# RF-Gen_Controller.net
KiCad netlist of a schematic drawn in EAGLE
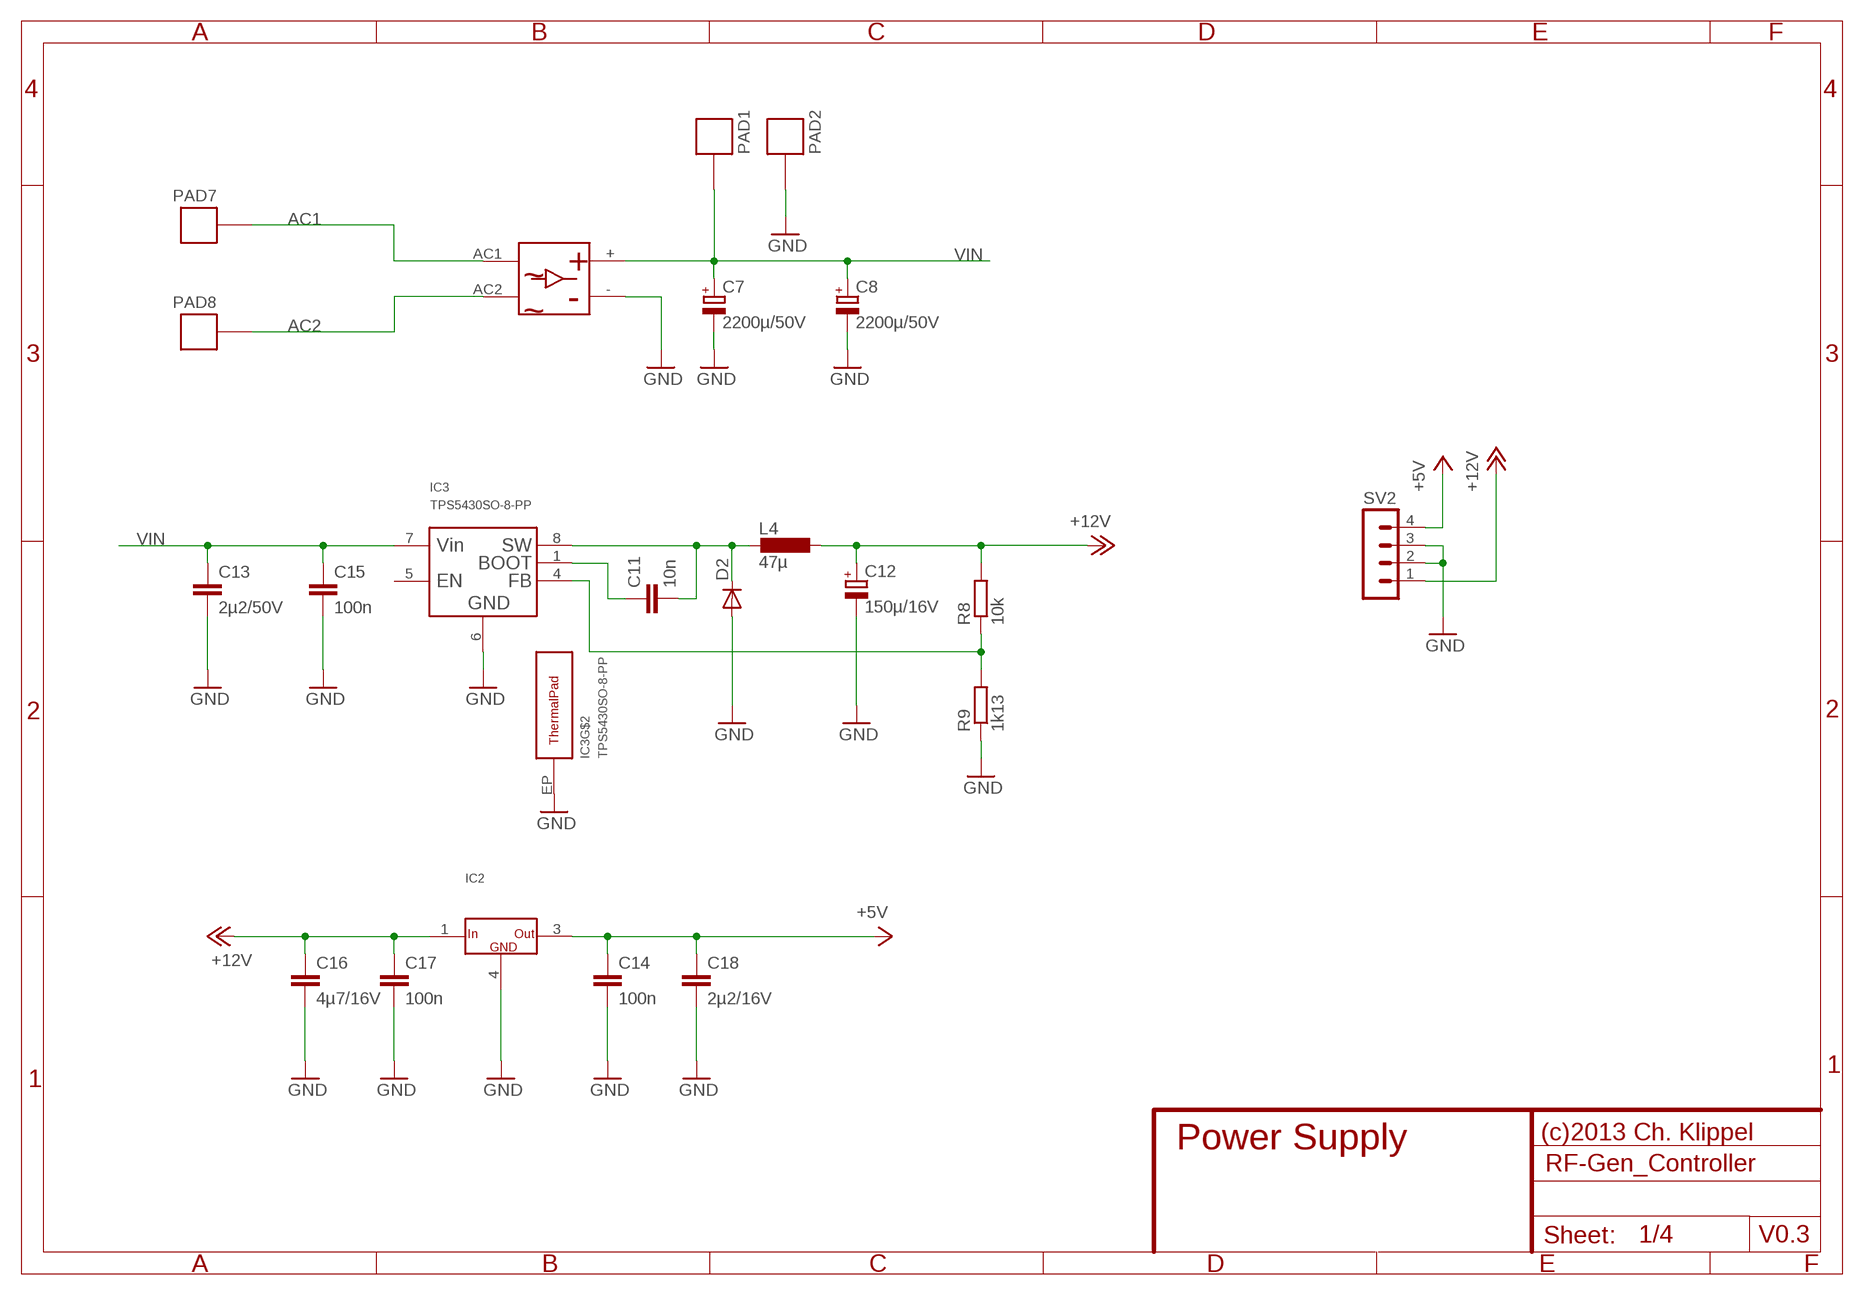
[diagram p0: schematic, sheet 1]
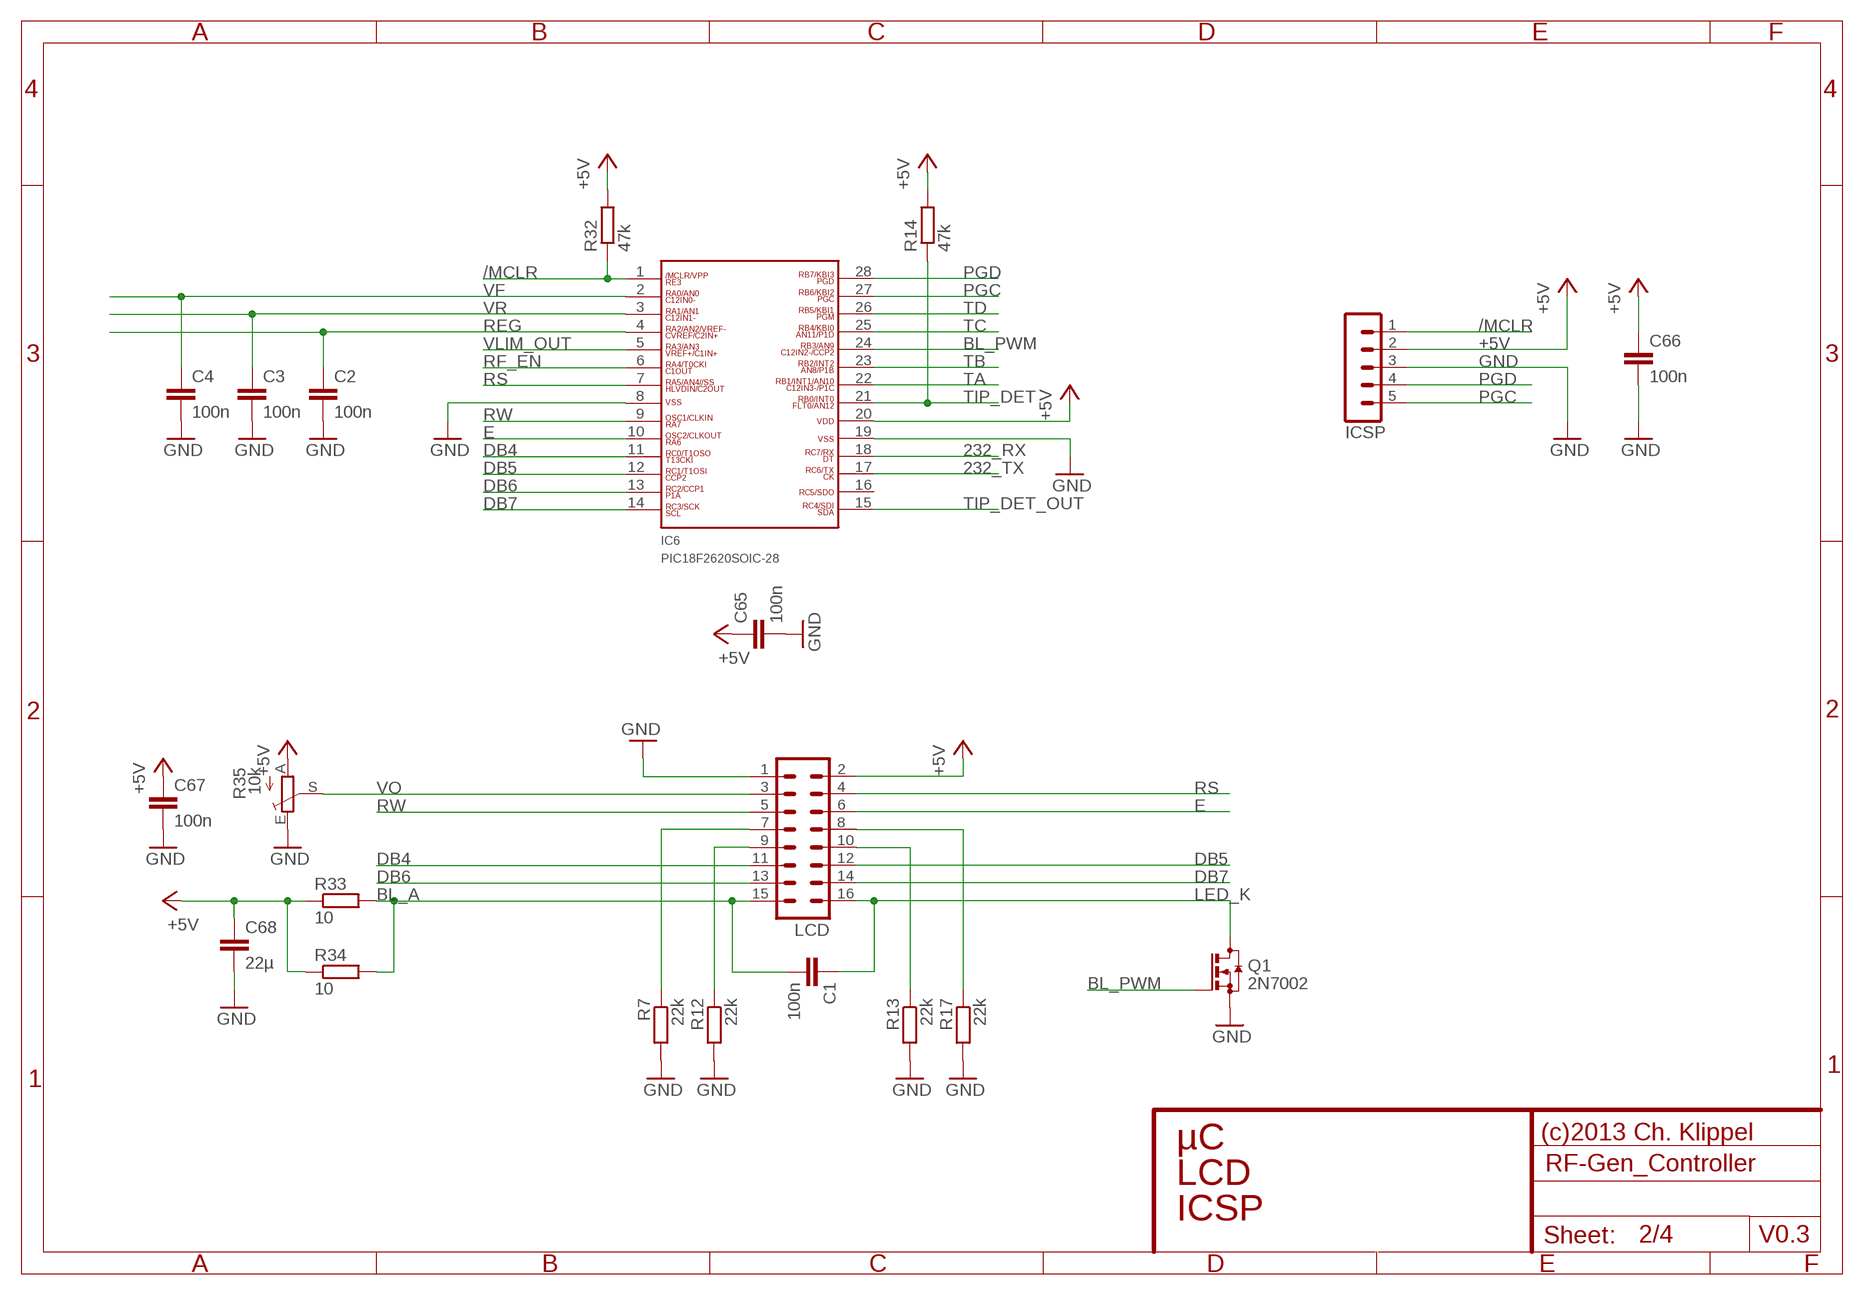
[diagram p1: schematic, sheet 2]
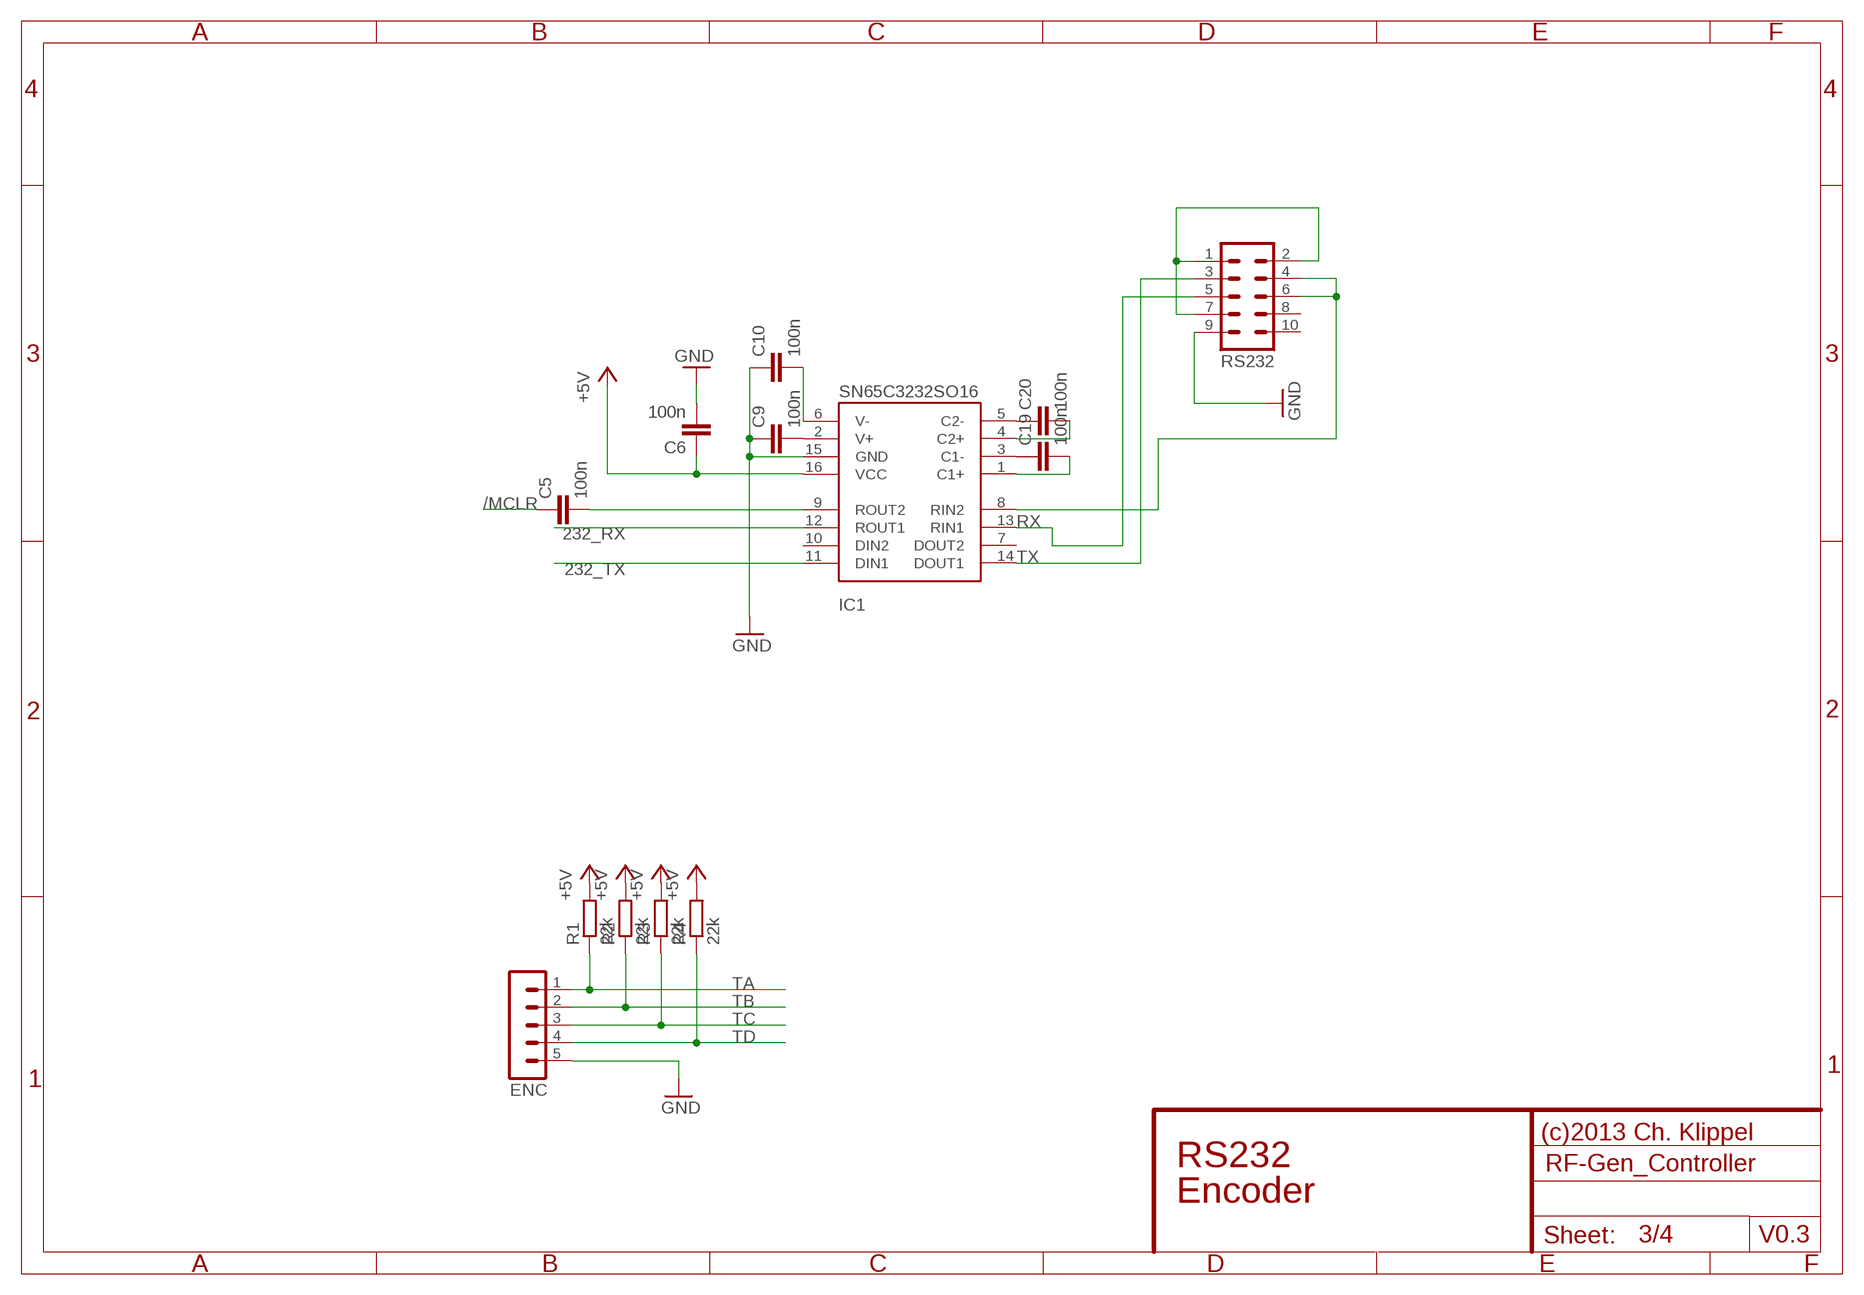
[diagram p2: schematic, sheet 3]
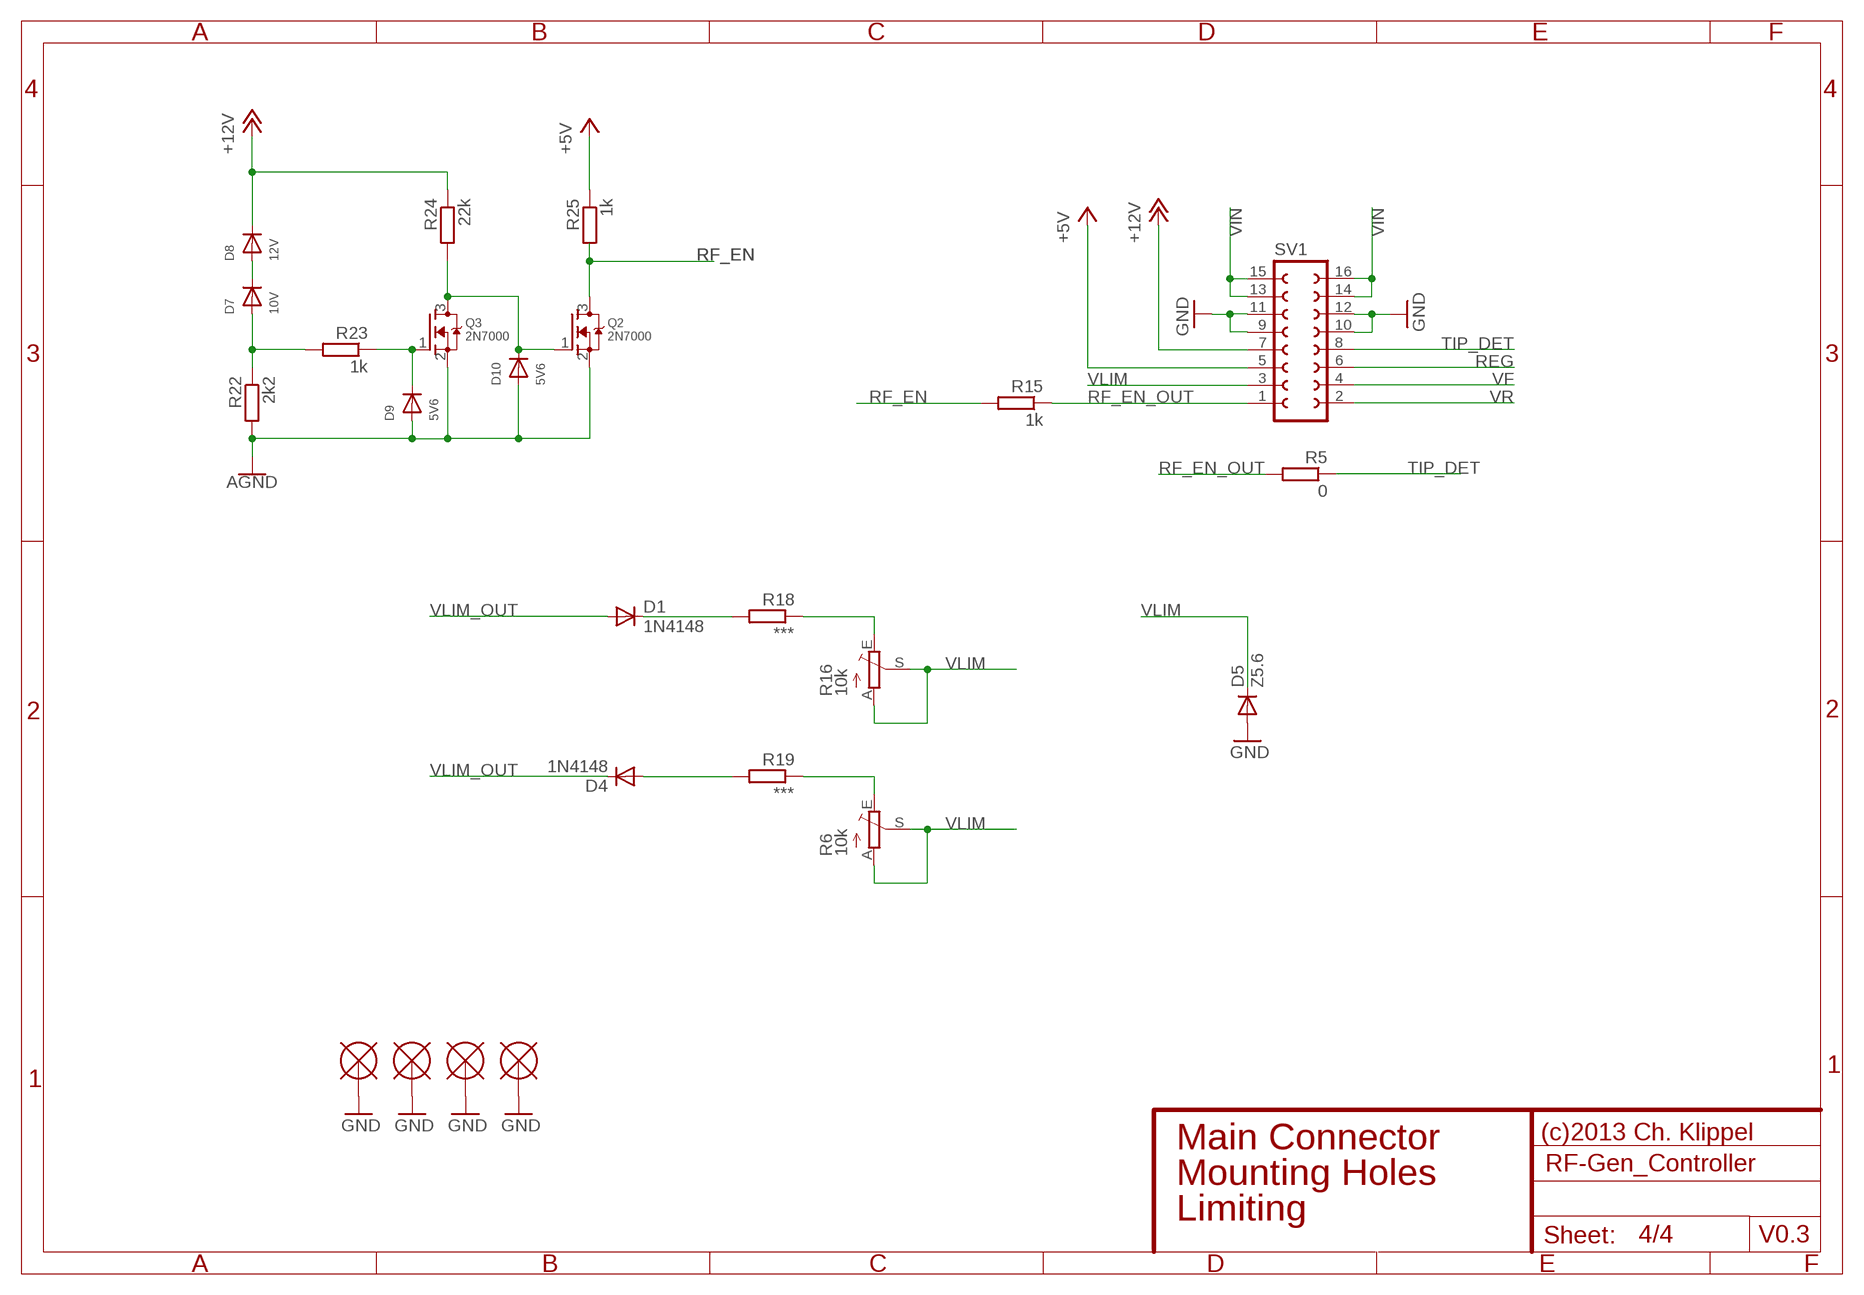
[diagram p3: schematic, sheet 4]

(export (version "E")
  (design (tool "Eeschema 10.0.6"))
  (components
    (comp (ref "BR1")
      (value "RECTIFIERGBJ_THT")
      (footprint "eagle-import:GBJ_THT")
      (libsource (lib "eagle-import") (part "RECTIFIERGBJ_THT"))
    )
    (comp (ref "C7")
      (value "2200µ/50V")
      (footprint "eagle-import:CAP_EEUHD1H_VERT2")
      (libsource (lib "eagle-import") (part "C-POL-EU-EEUHD1H_VERT2"))
    )
    (comp (ref "C8")
      (value "2200µ/50V")
      (footprint "eagle-import:CAP_EEUHD1H_VERT2")
      (libsource (lib "eagle-import") (part "C-POL-EU-EEUHD1H_VERT2"))
    )
    (comp (ref "C11")
      (value "10n")
      (footprint "eagle-import:C_1206_REFLOW")
      (libsource (lib "eagle-import") (part "C-EU-1206"))
    )
    (comp (ref "C12")
      (value "150µ/16V")
      (footprint "eagle-import:CAP_AL_100_108")
      (libsource (lib "eagle-import") (part "C-POL-EU-AL_100_108"))
    )
    (comp (ref "C13")
      (value "2µ2/50V")
      (footprint "eagle-import:C_1210_REFLOW")
      (libsource (lib "eagle-import") (part "C-EU-1210"))
    )
    (comp (ref "C14")
      (value "100n")
      (footprint "eagle-import:C_0805_REFLOW")
      (libsource (lib "eagle-import") (part "C-EU-0805"))
    )
    (comp (ref "C15")
      (value "100n")
      (footprint "eagle-import:C_0805_REFLOW")
      (libsource (lib "eagle-import") (part "C-EU-0805"))
    )
    (comp (ref "C16")
      (value "4µ7/16V")
      (footprint "eagle-import:C_1210_REFLOW")
      (libsource (lib "eagle-import") (part "C-EU-1210"))
    )
    (comp (ref "C17")
      (value "100n")
      (footprint "eagle-import:C_0805_REFLOW")
      (libsource (lib "eagle-import") (part "C-EU-0805"))
    )
    (comp (ref "C18")
      (value "2µ2/16V")
      (footprint "eagle-import:C_1210_REFLOW")
      (libsource (lib "eagle-import") (part "C-EU-1210"))
    )
    (comp (ref "D2")
      (value "DIODE-SMB")
      (footprint "eagle-import:SMB")
      (libsource (lib "eagle-import") (part "DIODE-SMB"))
    )
    (comp (ref "IC2")
      (value "VREG_3DPAK-3")
      (footprint "eagle-import:DPAK-3")
      (libsource (lib "eagle-import") (part "VREG_3DPAK-3"))
    )
    (comp (ref "IC3")
      (value "TPS5430SO-8-PP")
      (footprint "eagle-import:SO-8-PP")
      (libsource (lib "eagle-import") (part "TPS5430SO-8-PP"))
    )
    (comp (ref "L4")
      (value "47µ")
      (footprint "eagle-import:SSR1260")
      (libsource (lib "eagle-import") (part "L-EU-SSR1260"))
    )
    (comp (ref "PAD1")
      (value "SOLPAD5MM")
      (footprint "eagle-import:SOLPAD_5")
      (libsource (lib "eagle-import") (part "SOLPAD5MM"))
    )
    (comp (ref "PAD2")
      (value "SOLPAD5MM")
      (footprint "eagle-import:SOLPAD_5")
      (libsource (lib "eagle-import") (part "SOLPAD5MM"))
    )
    (comp (ref "PAD7")
      (value "SOLPAD5MM")
      (footprint "eagle-import:SOLPAD_5")
      (libsource (lib "eagle-import") (part "SOLPAD5MM"))
    )
    (comp (ref "PAD8")
      (value "SOLPAD5MM")
      (footprint "eagle-import:SOLPAD_5")
      (libsource (lib "eagle-import") (part "SOLPAD5MM"))
    )
    (comp (ref "R8")
      (value "10k")
      (footprint "eagle-import:R_0805_REFLOW")
      (libsource (lib "eagle-import") (part "R-EU-0805"))
    )
    (comp (ref "R9")
      (value "1k13")
      (footprint "eagle-import:R_0805_REFLOW")
      (libsource (lib "eagle-import") (part "R-EU-0805"))
    )
    (comp (ref "SV2")
      (value "MA04-1")
      (footprint "eagle-import:MA04-1")
      (libsource (lib "eagle-import") (part "MA04-1"))
    )
    (comp (ref "D1")
      (value "1N4148")
      (footprint "eagle-import:LL-34")
      (libsource (lib "eagle-import") (part "DIODE-LL-34"))
    )
    (comp (ref "D4")
      (value "1N4148")
      (footprint "eagle-import:LL-34")
      (libsource (lib "eagle-import") (part "DIODE-LL-34"))
    )
    (comp (ref "D5")
      (value "Z5.6")
      (footprint "eagle-import:LL-34")
      (libsource (lib "eagle-import") (part "DIODE-LL-34"))
    )
    (comp (ref "D7")
      (value "10V")
      (footprint "eagle-import:SOD-323F")
      (libsource (lib "eagle-import") (part "DIODESOD-323F"))
    )
    (comp (ref "D8")
      (value "12V")
      (footprint "eagle-import:SOD-323F")
      (libsource (lib "eagle-import") (part "DIODESOD-323F"))
    )
    (comp (ref "D9")
      (value "5V6")
      (footprint "eagle-import:SOD-323F")
      (libsource (lib "eagle-import") (part "DIODESOD-323F"))
    )
    (comp (ref "D10")
      (value "5V6")
      (footprint "eagle-import:SOD-323F")
      (libsource (lib "eagle-import") (part "DIODESOD-323F"))
    )
    (comp (ref "Q2")
      (value "2N7000")
      (footprint "eagle-import:SOT23")
      (libsource (lib "eagle-import") (part "MOSFET-NREFLOW"))
    )
    (comp (ref "Q3")
      (value "2N7000")
      (footprint "eagle-import:SOT23")
      (libsource (lib "eagle-import") (part "MOSFET-NREFLOW"))
    )
    (comp (ref "R5")
      (value "0")
      (footprint "eagle-import:R_0805_REFLOW")
      (libsource (lib "eagle-import") (part "R-EU-0805"))
    )
    (comp (ref "R6")
      (value "10k")
      (footprint "eagle-import:3364W")
      (libsource (lib "eagle-import") (part "TRIM_EU-3364W"))
    )
    (comp (ref "R15")
      (value "1k")
      (footprint "eagle-import:R_0805_REFLOW")
      (libsource (lib "eagle-import") (part "R-EU-0805"))
    )
    (comp (ref "R16")
      (value "10k")
      (footprint "eagle-import:3364W")
      (libsource (lib "eagle-import") (part "TRIM_EU-3364W"))
    )
    (comp (ref "R18")
      (value "***")
      (footprint "eagle-import:R_0805_REFLOW")
      (libsource (lib "eagle-import") (part "R-EU-0805"))
    )
    (comp (ref "R19")
      (value "***")
      (footprint "eagle-import:R_0805_REFLOW")
      (libsource (lib "eagle-import") (part "R-EU-0805"))
    )
    (comp (ref "R22")
      (value "2k2")
      (footprint "eagle-import:R_0805_REFLOW")
      (libsource (lib "eagle-import") (part "R-EU-0805"))
    )
    (comp (ref "R23")
      (value "1k")
      (footprint "eagle-import:R_0805_REFLOW")
      (libsource (lib "eagle-import") (part "R-EU-0805"))
    )
    (comp (ref "R24")
      (value "22k")
      (footprint "eagle-import:R_0805_REFLOW")
      (libsource (lib "eagle-import") (part "R-EU-0805"))
    )
    (comp (ref "R25")
      (value "1k")
      (footprint "eagle-import:R_0805_REFLOW")
      (libsource (lib "eagle-import") (part "R-EU-0805"))
    )
    (comp (ref "SV1")
      (value "FE08-2")
      (footprint "eagle-import:FE08-2")
      (libsource (lib "eagle-import") (part "FE08-2"))
    )
    (comp (ref "U$6")
      (value "MOUNTPADM3_WASHER")
      (footprint "eagle-import:PAD_M3_WASHER")
      (libsource (lib "eagle-import") (part "MOUNTPADM3_WASHER"))
    )
    (comp (ref "U$7")
      (value "MOUNTPADM3_WASHER")
      (footprint "eagle-import:PAD_M3_WASHER")
      (libsource (lib "eagle-import") (part "MOUNTPADM3_WASHER"))
    )
    (comp (ref "U$8")
      (value "MOUNTPADM3_WASHER")
      (footprint "eagle-import:PAD_M3_WASHER")
      (libsource (lib "eagle-import") (part "MOUNTPADM3_WASHER"))
    )
    (comp (ref "U$9")
      (value "MOUNTPADM3_WASHER")
      (footprint "eagle-import:PAD_M3_WASHER")
      (libsource (lib "eagle-import") (part "MOUNTPADM3_WASHER"))
    )
    (comp (ref "C5")
      (value "100n")
      (footprint "eagle-import:C_0805_REFLOW")
      (libsource (lib "eagle-import") (part "C-EU-0805"))
    )
    (comp (ref "C6")
      (value "100n")
      (footprint "eagle-import:C_0805_REFLOW")
      (libsource (lib "eagle-import") (part "C-EU-0805"))
    )
    (comp (ref "C9")
      (value "100n")
      (footprint "eagle-import:C_0805_REFLOW")
      (libsource (lib "eagle-import") (part "C-EU-0805"))
    )
    (comp (ref "C10")
      (value "100n")
      (footprint "eagle-import:C_0805_REFLOW")
      (libsource (lib "eagle-import") (part "C-EU-0805"))
    )
    (comp (ref "C19")
      (value "100n")
      (footprint "eagle-import:C_0805_REFLOW")
      (libsource (lib "eagle-import") (part "C-EU-0805"))
    )
    (comp (ref "C20")
      (value "100n")
      (footprint "eagle-import:C_0805_REFLOW")
      (libsource (lib "eagle-import") (part "C-EU-0805"))
    )
    (comp (ref "ENC")
      (value "MA05-1THT")
      (footprint "eagle-import:MA05-1")
      (libsource (lib "eagle-import") (part "MA05-1THT"))
    )
    (comp (ref "IC1")
      (value "SN65C3232SO16")
      (footprint "eagle-import:SO16")
      (libsource (lib "eagle-import") (part "SN65C3232SO16"))
    )
    (comp (ref "R1")
      (value "22k")
      (footprint "eagle-import:R_0805_REFLOW")
      (libsource (lib "eagle-import") (part "R-EU-0805"))
    )
    (comp (ref "R2")
      (value "22k")
      (footprint "eagle-import:R_0805_REFLOW")
      (libsource (lib "eagle-import") (part "R-EU-0805"))
    )
    (comp (ref "R3")
      (value "22k")
      (footprint "eagle-import:R_0805_REFLOW")
      (libsource (lib "eagle-import") (part "R-EU-0805"))
    )
    (comp (ref "R4")
      (value "22k")
      (footprint "eagle-import:R_0805_REFLOW")
      (libsource (lib "eagle-import") (part "R-EU-0805"))
    )
    (comp (ref "RS232")
      (value "ML10")
      (footprint "eagle-import:ML10")
      (libsource (lib "eagle-import") (part "ML10"))
    )
    (comp (ref "C1")
      (value "100n")
      (footprint "eagle-import:C_0805_REFLOW")
      (libsource (lib "eagle-import") (part "C-EU-0805"))
    )
    (comp (ref "C2")
      (value "100n")
      (footprint "eagle-import:C_0805_REFLOW")
      (libsource (lib "eagle-import") (part "C-EU-0805"))
    )
    (comp (ref "C3")
      (value "100n")
      (footprint "eagle-import:C_0805_REFLOW")
      (libsource (lib "eagle-import") (part "C-EU-0805"))
    )
    (comp (ref "C4")
      (value "100n")
      (footprint "eagle-import:C_0805_REFLOW")
      (libsource (lib "eagle-import") (part "C-EU-0805"))
    )
    (comp (ref "C65")
      (value "100n")
      (footprint "eagle-import:C_0805_REFLOW")
      (libsource (lib "eagle-import") (part "C-EU-0805"))
    )
    (comp (ref "C66")
      (value "100n")
      (footprint "eagle-import:C_0805_REFLOW")
      (libsource (lib "eagle-import") (part "C-EU-0805"))
    )
    (comp (ref "C67")
      (value "100n")
      (footprint "eagle-import:C_0805_REFLOW")
      (libsource (lib "eagle-import") (part "C-EU-0805"))
    )
    (comp (ref "C68")
      (value "22µ")
      (footprint "eagle-import:C_1206_REFLOW")
      (libsource (lib "eagle-import") (part "C-EU-1206"))
    )
    (comp (ref "IC6")
      (value "PIC18F2620SOIC-28")
      (footprint "eagle-import:SOIC-28")
      (libsource (lib "eagle-import") (part "PIC18F26K20SOIC-28"))
    )
    (comp (ref "ICSP")
      (value "MA05-1THT")
      (footprint "eagle-import:MA05-1")
      (libsource (lib "eagle-import") (part "MA05-1THT"))
    )
    (comp (ref "LCD")
      (value "ML16")
      (footprint "eagle-import:ML16")
      (libsource (lib "eagle-import") (part "ML16"))
    )
    (comp (ref "Q1")
      (value "2N7002")
      (footprint "eagle-import:SOT23")
      (libsource (lib "eagle-import") (part "BSS123"))
    )
    (comp (ref "R7")
      (value "22k")
      (footprint "eagle-import:R_0805_REFLOW")
      (libsource (lib "eagle-import") (part "R-EU-0805"))
    )
    (comp (ref "R12")
      (value "22k")
      (footprint "eagle-import:R_0805_REFLOW")
      (libsource (lib "eagle-import") (part "R-EU-0805"))
    )
    (comp (ref "R13")
      (value "22k")
      (footprint "eagle-import:R_0805_REFLOW")
      (libsource (lib "eagle-import") (part "R-EU-0805"))
    )
    (comp (ref "R14")
      (value "47k")
      (footprint "eagle-import:R_0805_REFLOW")
      (libsource (lib "eagle-import") (part "R-EU-0805"))
    )
    (comp (ref "R17")
      (value "22k")
      (footprint "eagle-import:R_0805_REFLOW")
      (libsource (lib "eagle-import") (part "R-EU-0805"))
    )
    (comp (ref "R32")
      (value "47k")
      (footprint "eagle-import:R_0805_REFLOW")
      (libsource (lib "eagle-import") (part "R-EU-0805"))
    )
    (comp (ref "R33")
      (value "10")
      (footprint "eagle-import:R_1206_REFLOW")
      (libsource (lib "eagle-import") (part "R-EU-1206"))
    )
    (comp (ref "R34")
      (value "10")
      (footprint "eagle-import:R_1206_REFLOW")
      (libsource (lib "eagle-import") (part "R-EU-1206"))
    )
    (comp (ref "R35")
      (value "10k")
      (footprint "eagle-import:3364W")
      (libsource (lib "eagle-import") (part "TRIM_EU-3364W"))
    )
  )
  (nets
    (net (code "1") (name "+5V") (class "Default")
      (node (ref "C14") (pin "P$1") (pinfunction "1_P$1") (pintype "passive"))
      (node (ref "C18") (pin "P$1") (pinfunction "1_P$1") (pintype "passive"))
      (node (ref "C6") (pin "P$1") (pinfunction "1_P$1") (pintype "passive"))
      (node (ref "C65") (pin "P$1") (pinfunction "1_P$1") (pintype "passive"))
      (node (ref "C66") (pin "P$1") (pinfunction "1_P$1") (pintype "passive"))
      (node (ref "C67") (pin "P$1") (pinfunction "1_P$1") (pintype "passive"))
      (node (ref "C68") (pin "P$1") (pinfunction "1_P$1") (pintype "passive"))
      (node (ref "IC1") (pin "16") (pinfunction "VCC_16") (pintype "bidirectional"))
      (node (ref "IC2") (pin "3") (pinfunction "OUT_3") (pintype "bidirectional"))
      (node (ref "IC6") (pin "20") (pinfunction "P$20_20") (pintype "bidirectional"))
      (node (ref "ICSP") (pin "2") (pinfunction "2_2") (pintype "passive"))
      (node (ref "LCD") (pin "2") (pinfunction "2_2") (pintype "passive"))
      (node (ref "R1") (pin "P$2") (pinfunction "2_P$2") (pintype "passive"))
      (node (ref "R14") (pin "P$2") (pinfunction "2_P$2") (pintype "passive"))
      (node (ref "R2") (pin "P$2") (pinfunction "2_P$2") (pintype "passive"))
      (node (ref "R25") (pin "P$1") (pinfunction "1_P$1") (pintype "passive"))
      (node (ref "R3") (pin "P$2") (pinfunction "2_P$2") (pintype "passive"))
      (node (ref "R32") (pin "P$2") (pinfunction "2_P$2") (pintype "passive"))
      (node (ref "R33") (pin "P$1") (pinfunction "1_P$1") (pintype "passive"))
      (node (ref "R34") (pin "P$1") (pinfunction "1_P$1") (pintype "passive"))
      (node (ref "R35") (pin "A") (pinfunction "A_A") (pintype "passive"))
      (node (ref "R4") (pin "P$2") (pinfunction "2_P$2") (pintype "passive"))
      (node (ref "SV1") (pin "5") (pinfunction "5_5") (pintype "passive"))
      (node (ref "SV2") (pin "4") (pinfunction "4_4") (pintype "passive"))
    )
    (net (code "2") (name "+12V") (class "Default")
      (node (ref "C12") (pin "+") (pinfunction "+_+") (pintype "passive"))
      (node (ref "C16") (pin "P$1") (pinfunction "1_P$1") (pintype "passive"))
      (node (ref "C17") (pin "P$1") (pinfunction "1_P$1") (pintype "passive"))
      (node (ref "D8") (pin "C") (pinfunction "C_C") (pintype "passive"))
      (node (ref "IC2") (pin "1") (pinfunction "IN_1") (pintype "bidirectional"))
      (node (ref "L4") (pin "1") (pinfunction "1_1") (pintype "passive"))
      (node (ref "R24") (pin "P$1") (pinfunction "1_P$1") (pintype "passive"))
      (node (ref "R8") (pin "P$2") (pinfunction "2_P$2") (pintype "passive"))
      (node (ref "SV1") (pin "7") (pinfunction "7_7") (pintype "passive"))
      (node (ref "SV2") (pin "1") (pinfunction "1_1") (pintype "passive"))
    )
    (net (code "3") (name "232_RX") (class "Default")
      (node (ref "IC1") (pin "12") (pinfunction "ROUT1_12") (pintype "bidirectional"))
      (node (ref "IC6") (pin "18") (pinfunction "P$18_18") (pintype "bidirectional"))
    )
    (net (code "4") (name "232_TX") (class "Default")
      (node (ref "IC1") (pin "11") (pinfunction "DIN1_11") (pintype "bidirectional"))
      (node (ref "IC6") (pin "17") (pinfunction "P$17_17") (pintype "bidirectional"))
    )
    (net (code "5") (name "AC1") (class "Default")
      (node (ref "BR1") (pin "AC1") (pinfunction "AC1_AC1") (pintype "bidirectional"))
      (node (ref "PAD7") (pin "P$1") (pinfunction "P$1_P$1") (pintype "bidirectional"))
    )
    (net (code "6") (name "AC2") (class "Default")
      (node (ref "BR1") (pin "AC2") (pinfunction "AC2_AC2") (pintype "bidirectional"))
      (node (ref "PAD8") (pin "P$1") (pinfunction "P$1_P$1") (pintype "bidirectional"))
    )
    (net (code "7") (name "AGND") (class "Default")
      (node (ref "D10") (pin "A") (pinfunction "A_A") (pintype "passive"))
      (node (ref "D9") (pin "A") (pinfunction "A_A") (pintype "passive"))
      (node (ref "Q2") (pin "2") (pinfunction "S_2") (pintype "bidirectional"))
      (node (ref "Q3") (pin "2") (pinfunction "S_2") (pintype "bidirectional"))
      (node (ref "R22") (pin "P$2") (pinfunction "2_P$2") (pintype "passive"))
    )
    (net (code "8") (name "BL_A") (class "Default")
      (node (ref "C1") (pin "P$2") (pinfunction "2_P$2") (pintype "passive"))
      (node (ref "LCD") (pin "15") (pinfunction "15_15") (pintype "passive"))
      (node (ref "R33") (pin "P$2") (pinfunction "2_P$2") (pintype "passive"))
      (node (ref "R34") (pin "P$2") (pinfunction "2_P$2") (pintype "passive"))
    )
    (net (code "9") (name "BL_PWM") (class "Default")
      (node (ref "IC6") (pin "24") (pinfunction "P$24_24") (pintype "bidirectional"))
      (node (ref "Q1") (pin "1") (pinfunction "G_1") (pintype "passive"))
    )
    (net (code "10") (name "DB4") (class "Default")
      (node (ref "IC6") (pin "11") (pinfunction "P$11_11") (pintype "bidirectional"))
      (node (ref "LCD") (pin "11") (pinfunction "11_11") (pintype "passive"))
    )
    (net (code "11") (name "DB5") (class "Default")
      (node (ref "IC6") (pin "12") (pinfunction "P$12_12") (pintype "bidirectional"))
      (node (ref "LCD") (pin "12") (pinfunction "12_12") (pintype "passive"))
    )
    (net (code "12") (name "DB6") (class "Default")
      (node (ref "IC6") (pin "13") (pinfunction "P$13_13") (pintype "bidirectional"))
      (node (ref "LCD") (pin "13") (pinfunction "13_13") (pintype "passive"))
    )
    (net (code "13") (name "DB7") (class "Default")
      (node (ref "IC6") (pin "14") (pinfunction "P$14_14") (pintype "bidirectional"))
      (node (ref "LCD") (pin "14") (pinfunction "14_14") (pintype "passive"))
    )
    (net (code "14") (name "E") (class "Default")
      (node (ref "IC6") (pin "10") (pinfunction "P$10_10") (pintype "bidirectional"))
      (node (ref "LCD") (pin "6") (pinfunction "6_6") (pintype "passive"))
    )
    (net (code "15") (name "GND") (class "Default")
      (node (ref "BR1") (pin "-") (pinfunction "-_-") (pintype "bidirectional"))
      (node (ref "C10") (pin "P$1") (pinfunction "1_P$1") (pintype "passive"))
      (node (ref "C12") (pin "-") (pinfunction "-_-") (pintype "passive"))
      (node (ref "C13") (pin "P$2") (pinfunction "2_P$2") (pintype "passive"))
      (node (ref "C14") (pin "P$2") (pinfunction "2_P$2") (pintype "passive"))
      (node (ref "C15") (pin "P$2") (pinfunction "2_P$2") (pintype "passive"))
      (node (ref "C16") (pin "P$2") (pinfunction "2_P$2") (pintype "passive"))
      (node (ref "C17") (pin "P$2") (pinfunction "2_P$2") (pintype "passive"))
      (node (ref "C18") (pin "P$2") (pinfunction "2_P$2") (pintype "passive"))
      (node (ref "C2") (pin "P$2") (pinfunction "2_P$2") (pintype "passive"))
      (node (ref "C3") (pin "P$2") (pinfunction "2_P$2") (pintype "passive"))
      (node (ref "C4") (pin "P$2") (pinfunction "2_P$2") (pintype "passive"))
      (node (ref "C6") (pin "P$2") (pinfunction "2_P$2") (pintype "passive"))
      (node (ref "C65") (pin "P$2") (pinfunction "2_P$2") (pintype "passive"))
      (node (ref "C66") (pin "P$2") (pinfunction "2_P$2") (pintype "passive"))
      (node (ref "C67") (pin "P$2") (pinfunction "2_P$2") (pintype "passive"))
      (node (ref "C68") (pin "P$2") (pinfunction "2_P$2") (pintype "passive"))
      (node (ref "C7") (pin "-") (pinfunction "-_-") (pintype "passive"))
      (node (ref "C8") (pin "-") (pinfunction "-_-") (pintype "passive"))
      (node (ref "C9") (pin "P$1") (pinfunction "1_P$1") (pintype "passive"))
      (node (ref "D2") (pin "A") (pinfunction "A_A") (pintype "passive"))
      (node (ref "D5") (pin "A") (pinfunction "A_A") (pintype "passive"))
      (node (ref "ENC") (pin "5") (pinfunction "5_5") (pintype "passive"))
      (node (ref "IC1") (pin "15") (pinfunction "GND_15") (pintype "bidirectional"))
      (node (ref "IC2") (pin "4") (pinfunction "GND_4") (pintype "bidirectional"))
      (node (ref "IC3") (pin "6") (pinfunction "GND_6") (pintype "bidirectional"))
      (node (ref "IC3") (pin "EP") (pinfunction "THERMALPAD_EP") (pintype "bidirectional"))
      (node (ref "IC6") (pin "19") (pinfunction "P$19_19") (pintype "bidirectional"))
      (node (ref "IC6") (pin "8") (pinfunction "P$8_8") (pintype "bidirectional"))
      (node (ref "ICSP") (pin "3") (pinfunction "3_3") (pintype "passive"))
      (node (ref "LCD") (pin "1") (pinfunction "1_1") (pintype "passive"))
      (node (ref "PAD2") (pin "P$1") (pinfunction "P$1_P$1") (pintype "bidirectional"))
      (node (ref "Q1") (pin "2") (pinfunction "S_2") (pintype "passive"))
      (node (ref "R12") (pin "P$2") (pinfunction "2_P$2") (pintype "passive"))
      (node (ref "R13") (pin "P$2") (pinfunction "2_P$2") (pintype "passive"))
      (node (ref "R17") (pin "P$2") (pinfunction "2_P$2") (pintype "passive"))
      (node (ref "R35") (pin "E") (pinfunction "E_E") (pintype "passive"))
      (node (ref "R7") (pin "P$2") (pinfunction "2_P$2") (pintype "passive"))
      (node (ref "R9") (pin "P$1") (pinfunction "1_P$1") (pintype "passive"))
      (node (ref "RS232") (pin "9") (pinfunction "9_9") (pintype "passive"))
      (node (ref "SV1") (pin "10") (pinfunction "10_10") (pintype "passive"))
      (node (ref "SV1") (pin "11") (pinfunction "11_11") (pintype "passive"))
      (node (ref "SV1") (pin "12") (pinfunction "12_12") (pintype "passive"))
      (node (ref "SV1") (pin "9") (pinfunction "9_9") (pintype "passive"))
      (node (ref "SV2") (pin "2") (pinfunction "2_2") (pintype "passive"))
      (node (ref "SV2") (pin "3") (pinfunction "3_3") (pintype "passive"))
      (node (ref "U$6") (pin "P$1") (pinfunction "P$1_P$1") (pintype "bidirectional"))
      (node (ref "U$7") (pin "P$1") (pinfunction "P$1_P$1") (pintype "bidirectional"))
      (node (ref "U$8") (pin "P$1") (pinfunction "P$1_P$1") (pintype "bidirectional"))
      (node (ref "U$9") (pin "P$1") (pinfunction "P$1_P$1") (pintype "bidirectional"))
    )
    (net (code "16") (name "LED_K") (class "Default")
      (node (ref "C1") (pin "P$1") (pinfunction "1_P$1") (pintype "passive"))
      (node (ref "LCD") (pin "16") (pinfunction "16_16") (pintype "passive"))
      (node (ref "Q1") (pin "3") (pinfunction "D_3") (pintype "passive"))
    )
    (net (code "17") (name "Net-(C5-2)") (class "Default")
      (node (ref "C5") (pin "P$2") (pinfunction "2_P$2") (pintype "passive"))
      (node (ref "IC1") (pin "9") (pinfunction "ROUT2_9") (pintype "bidirectional"))
    )
    (net (code "18") (name "Net-(C9-2)") (class "Default")
      (node (ref "C9") (pin "P$2") (pinfunction "2_P$2") (pintype "passive"))
      (node (ref "IC1") (pin "2") (pinfunction "V+_2") (pintype "bidirectional"))
    )
    (net (code "19") (name "Net-(C10-2)") (class "Default")
      (node (ref "C10") (pin "P$2") (pinfunction "2_P$2") (pintype "passive"))
      (node (ref "IC1") (pin "6") (pinfunction "V-_6") (pintype "bidirectional"))
    )
    (net (code "20") (name "Net-(C11-1)") (class "Default")
      (node (ref "C11") (pin "P$1") (pinfunction "1_P$1") (pintype "passive"))
      (node (ref "IC3") (pin "1") (pinfunction "BOOT_1") (pintype "bidirectional"))
    )
    (net (code "21") (name "Net-(C11-2)") (class "Default")
      (node (ref "C11") (pin "P$2") (pinfunction "2_P$2") (pintype "passive"))
      (node (ref "D2") (pin "C") (pinfunction "C_C") (pintype "passive"))
      (node (ref "IC3") (pin "8") (pinfunction "SW_8") (pintype "bidirectional"))
      (node (ref "L4") (pin "2") (pinfunction "2_2") (pintype "passive"))
    )
    (net (code "22") (name "Net-(C19-1)") (class "Default")
      (node (ref "C19") (pin "P$1") (pinfunction "1_P$1") (pintype "passive"))
      (node (ref "IC1") (pin "3") (pinfunction "C1-_3") (pintype "bidirectional"))
    )
    (net (code "23") (name "Net-(C19-2)") (class "Default")
      (node (ref "C19") (pin "P$2") (pinfunction "2_P$2") (pintype "passive"))
      (node (ref "IC1") (pin "1") (pinfunction "C1+_1") (pintype "bidirectional"))
    )
    (net (code "24") (name "Net-(C20-1)") (class "Default")
      (node (ref "C20") (pin "P$1") (pinfunction "1_P$1") (pintype "passive"))
      (node (ref "IC1") (pin "5") (pinfunction "C2-_5") (pintype "bidirectional"))
    )
    (net (code "25") (name "Net-(C20-2)") (class "Default")
      (node (ref "C20") (pin "P$2") (pinfunction "2_P$2") (pintype "passive"))
      (node (ref "IC1") (pin "4") (pinfunction "C2+_4") (pintype "bidirectional"))
    )
    (net (code "26") (name "Net-(D7-PadC)") (class "Default")
      (node (ref "D7") (pin "C") (pinfunction "C_C") (pintype "passive"))
      (node (ref "D8") (pin "A") (pinfunction "A_A") (pintype "passive"))
    )
    (net (code "27") (name "Net-(IC1-RIN2)") (class "Default")
      (node (ref "IC1") (pin "8") (pinfunction "RIN2_8") (pintype "bidirectional"))
      (node (ref "RS232") (pin "4") (pinfunction "4_4") (pintype "passive"))
      (node (ref "RS232") (pin "6") (pinfunction "6_6") (pintype "passive"))
    )
    (net (code "28") (name "Net-(IC3A-FB)") (class "Default")
      (node (ref "IC3") (pin "4") (pinfunction "FB_4") (pintype "bidirectional"))
      (node (ref "R8") (pin "P$1") (pinfunction "1_P$1") (pintype "passive"))
      (node (ref "R9") (pin "P$2") (pinfunction "2_P$2") (pintype "passive"))
    )
    (net (code "29") (name "Net-(Q2-G)") (class "Default")
      (node (ref "D10") (pin "C") (pinfunction "C_C") (pintype "passive"))
      (node (ref "Q2") (pin "1") (pinfunction "G_1") (pintype "bidirectional"))
      (node (ref "Q3") (pin "3") (pinfunction "D_3") (pintype "bidirectional"))
      (node (ref "R24") (pin "P$2") (pinfunction "2_P$2") (pintype "passive"))
    )
    (net (code "30") (name "Net-(Q3-G)") (class "Default")
      (node (ref "D9") (pin "C") (pinfunction "C_C") (pintype "passive"))
      (node (ref "Q3") (pin "1") (pinfunction "G_1") (pintype "bidirectional"))
      (node (ref "R23") (pin "P$1") (pinfunction "1_P$1") (pintype "passive"))
    )
    (net (code "31") (name "Net-(R7-1)") (class "Default")
      (node (ref "LCD") (pin "7") (pinfunction "7_7") (pintype "passive"))
      (node (ref "R7") (pin "P$1") (pinfunction "1_P$1") (pintype "passive"))
    )
    (net (code "32") (name "Net-(R12-1)") (class "Default")
      (node (ref "LCD") (pin "9") (pinfunction "9_9") (pintype "passive"))
      (node (ref "R12") (pin "P$1") (pinfunction "1_P$1") (pintype "passive"))
    )
    (net (code "33") (name "Net-(R13-1)") (class "Default")
      (node (ref "LCD") (pin "10") (pinfunction "10_10") (pintype "passive"))
      (node (ref "R13") (pin "P$1") (pinfunction "1_P$1") (pintype "passive"))
    )
    (net (code "34") (name "Net-(R17-1)") (class "Default")
      (node (ref "LCD") (pin "8") (pinfunction "8_8") (pintype "passive"))
      (node (ref "R17") (pin "P$1") (pinfunction "1_P$1") (pintype "passive"))
    )
    (net (code "35") (name "Net-(R18-1)") (class "Default")
      (node (ref "R16") (pin "E") (pinfunction "E_E") (pintype "passive"))
      (node (ref "R18") (pin "P$1") (pinfunction "1_P$1") (pintype "passive"))
    )
    (net (code "36") (name "Net-(R18-2)") (class "Default")
      (node (ref "D1") (pin "C") (pinfunction "C_C") (pintype "passive"))
      (node (ref "R18") (pin "P$2") (pinfunction "2_P$2") (pintype "passive"))
    )
    (net (code "37") (name "Net-(R19-1)") (class "Default")
      (node (ref "R19") (pin "P$1") (pinfunction "1_P$1") (pintype "passive"))
      (node (ref "R6") (pin "E") (pinfunction "E_E") (pintype "passive"))
    )
    (net (code "38") (name "Net-(R19-2)") (class "Default")
      (node (ref "D4") (pin "A") (pinfunction "A_A") (pintype "passive"))
      (node (ref "R19") (pin "P$2") (pinfunction "2_P$2") (pintype "passive"))
    )
    (net (code "39") (name "Net-(R22-1)") (class "Default")
      (node (ref "D7") (pin "A") (pinfunction "A_A") (pintype "passive"))
      (node (ref "R22") (pin "P$1") (pinfunction "1_P$1") (pintype "passive"))
      (node (ref "R23") (pin "P$2") (pinfunction "2_P$2") (pintype "passive"))
    )
    (net (code "40") (name "Net-(RS232-Pad1)") (class "Default")
      (node (ref "RS232") (pin "1") (pinfunction "1_1") (pintype "passive"))
      (node (ref "RS232") (pin "2") (pinfunction "2_2") (pintype "passive"))
      (node (ref "RS232") (pin "7") (pinfunction "7_7") (pintype "passive"))
    )
    (net (code "41") (name "PGC") (class "Default")
      (node (ref "IC6") (pin "27") (pinfunction "P$27_27") (pintype "bidirectional"))
      (node (ref "ICSP") (pin "5") (pinfunction "5_5") (pintype "passive"))
    )
    (net (code "42") (name "PGD") (class "Default")
      (node (ref "IC6") (pin "28") (pinfunction "P$28_28") (pintype "bidirectional"))
      (node (ref "ICSP") (pin "4") (pinfunction "4_4") (pintype "passive"))
    )
    (net (code "43") (name "REG") (class "Default")
      (node (ref "C2") (pin "P$1") (pinfunction "1_P$1") (pintype "passive"))
      (node (ref "IC6") (pin "4") (pinfunction "P$4_4") (pintype "bidirectional"))
      (node (ref "SV1") (pin "6") (pinfunction "6_6") (pintype "passive"))
    )
    (net (code "44") (name "RF_EN") (class "Default")
      (node (ref "IC6") (pin "6") (pinfunction "P$6_6") (pintype "bidirectional"))
      (node (ref "Q2") (pin "3") (pinfunction "D_3") (pintype "bidirectional"))
      (node (ref "R15") (pin "P$2") (pinfunction "2_P$2") (pintype "passive"))
      (node (ref "R25") (pin "P$2") (pinfunction "2_P$2") (pintype "passive"))
    )
    (net (code "45") (name "RF_EN_OUT") (class "Default")
      (node (ref "R15") (pin "P$1") (pinfunction "1_P$1") (pintype "passive"))
      (node (ref "R5") (pin "P$2") (pinfunction "2_P$2") (pintype "passive"))
      (node (ref "SV1") (pin "1") (pinfunction "1_1") (pintype "passive"))
    )
    (net (code "46") (name "RS") (class "Default")
      (node (ref "IC6") (pin "7") (pinfunction "P$7_7") (pintype "bidirectional"))
      (node (ref "LCD") (pin "4") (pinfunction "4_4") (pintype "passive"))
    )
    (net (code "47") (name "RW") (class "Default")
      (node (ref "IC6") (pin "9") (pinfunction "P$9_9") (pintype "bidirectional"))
      (node (ref "LCD") (pin "5") (pinfunction "5_5") (pintype "passive"))
    )
    (net (code "48") (name "RX") (class "Default")
      (node (ref "IC1") (pin "13") (pinfunction "RIN1_13") (pintype "bidirectional"))
      (node (ref "RS232") (pin "5") (pinfunction "5_5") (pintype "passive"))
    )
    (net (code "49") (name "TA") (class "Default")
      (node (ref "ENC") (pin "1") (pinfunction "1_1") (pintype "passive"))
      (node (ref "IC6") (pin "22") (pinfunction "P$22_22") (pintype "bidirectional"))
      (node (ref "R1") (pin "P$1") (pinfunction "1_P$1") (pintype "passive"))
    )
    (net (code "50") (name "TB") (class "Default")
      (node (ref "ENC") (pin "2") (pinfunction "2_2") (pintype "passive"))
      (node (ref "IC6") (pin "23") (pinfunction "P$23_23") (pintype "bidirectional"))
      (node (ref "R2") (pin "P$1") (pinfunction "1_P$1") (pintype "passive"))
    )
    (net (code "51") (name "TC") (class "Default")
      (node (ref "ENC") (pin "3") (pinfunction "3_3") (pintype "passive"))
      (node (ref "IC6") (pin "25") (pinfunction "P$25_25") (pintype "bidirectional"))
      (node (ref "R3") (pin "P$1") (pinfunction "1_P$1") (pintype "passive"))
    )
    (net (code "52") (name "TD") (class "Default")
      (node (ref "ENC") (pin "4") (pinfunction "4_4") (pintype "passive"))
      (node (ref "IC6") (pin "26") (pinfunction "P$26_26") (pintype "bidirectional"))
      (node (ref "R4") (pin "P$1") (pinfunction "1_P$1") (pintype "passive"))
    )
    (net (code "53") (name "TIP_DET") (class "Default")
      (node (ref "IC6") (pin "21") (pinfunction "P$21_21") (pintype "bidirectional"))
      (node (ref "R14") (pin "P$1") (pinfunction "1_P$1") (pintype "passive"))
      (node (ref "R5") (pin "P$1") (pinfunction "1_P$1") (pintype "passive"))
      (node (ref "SV1") (pin "8") (pinfunction "8_8") (pintype "passive"))
    )
    (net (code "54") (name "TIP_DET_OUT") (class "Default")
      (node (ref "IC6") (pin "15") (pinfunction "P$15_15") (pintype "bidirectional"))
    )
    (net (code "55") (name "TX") (class "Default")
      (node (ref "IC1") (pin "14") (pinfunction "DOUT1_14") (pintype "bidirectional"))
      (node (ref "RS232") (pin "3") (pinfunction "3_3") (pintype "passive"))
    )
    (net (code "56") (name "VF") (class "Default")
      (node (ref "C4") (pin "P$1") (pinfunction "1_P$1") (pintype "passive"))
      (node (ref "IC6") (pin "2") (pinfunction "P$2_2") (pintype "bidirectional"))
      (node (ref "SV1") (pin "4") (pinfunction "4_4") (pintype "passive"))
    )
    (net (code "57") (name "VIN") (class "Default")
      (node (ref "BR1") (pin "+") (pinfunction "+_+") (pintype "bidirectional"))
      (node (ref "C13") (pin "P$1") (pinfunction "1_P$1") (pintype "passive"))
      (node (ref "C15") (pin "P$1") (pinfunction "1_P$1") (pintype "passive"))
      (node (ref "C7") (pin "+") (pinfunction "+_+") (pintype "passive"))
      (node (ref "C8") (pin "+") (pinfunction "+_+") (pintype "passive"))
      (node (ref "IC3") (pin "7") (pinfunction "VIN_7") (pintype "bidirectional"))
      (node (ref "PAD1") (pin "P$1") (pinfunction "P$1_P$1") (pintype "bidirectional"))
      (node (ref "SV1") (pin "13") (pinfunction "13_13") (pintype "passive"))
      (node (ref "SV1") (pin "14") (pinfunction "14_14") (pintype "passive"))
      (node (ref "SV1") (pin "15") (pinfunction "15_15") (pintype "passive"))
      (node (ref "SV1") (pin "16") (pinfunction "16_16") (pintype "passive"))
    )
    (net (code "58") (name "VLIM") (class "Default")
      (node (ref "D5") (pin "C") (pinfunction "C_C") (pintype "passive"))
      (node (ref "R16") (pin "A") (pinfunction "A_A") (pintype "passive"))
      (node (ref "R16") (pin "S") (pinfunction "S_S") (pintype "passive"))
      (node (ref "R6") (pin "A") (pinfunction "A_A") (pintype "passive"))
      (node (ref "R6") (pin "S") (pinfunction "S_S") (pintype "passive"))
      (node (ref "SV1") (pin "3") (pinfunction "3_3") (pintype "passive"))
    )
    (net (code "59") (name "VLIM_OUT") (class "Default")
      (node (ref "D1") (pin "A") (pinfunction "A_A") (pintype "passive"))
      (node (ref "D4") (pin "C") (pinfunction "C_C") (pintype "passive"))
      (node (ref "IC6") (pin "5") (pinfunction "P$5_5") (pintype "bidirectional"))
    )
    (net (code "60") (name "VO") (class "Default")
      (node (ref "LCD") (pin "3") (pinfunction "3_3") (pintype "passive"))
      (node (ref "R35") (pin "S") (pinfunction "S_S") (pintype "passive"))
    )
    (net (code "61") (name "VR") (class "Default")
      (node (ref "C3") (pin "P$1") (pinfunction "1_P$1") (pintype "passive"))
      (node (ref "IC6") (pin "3") (pinfunction "P$3_3") (pintype "bidirectional"))
      (node (ref "SV1") (pin "2") (pinfunction "2_2") (pintype "passive"))
    )
    (net (code "62") (name "unconnected-(IC1-DIN2-Pad10)") (class "Default")
      (node (ref "IC1") (pin "10") (pinfunction "DIN2_10") (pintype "bidirectional"))
    )
    (net (code "63") (name "unconnected-(IC1-DOUT2-Pad7)") (class "Default")
      (node (ref "IC1") (pin "7") (pinfunction "DOUT2_7") (pintype "bidirectional"))
    )
    (net (code "64") (name "unconnected-(IC3A-EN-Pad5)") (class "Default")
      (node (ref "IC3") (pin "5") (pinfunction "EN_5") (pintype "bidirectional"))
    )
    (net (code "65") (name "unconnected-(IC6-P$16-Pad16)") (class "Default")
      (node (ref "IC6") (pin "16") (pinfunction "P$16_16") (pintype "bidirectional"))
    )
    (net (code "66") (name "unconnected-(RS232-Pad8)") (class "Default")
      (node (ref "RS232") (pin "8") (pinfunction "8_8") (pintype "passive"))
    )
    (net (code "67") (name "unconnected-(RS232-Pad10)") (class "Default")
      (node (ref "RS232") (pin "10") (pinfunction "10_10") (pintype "passive"))
    )
    (net (code "68") (name "{slash}MCLR") (class "Default")
      (node (ref "C5") (pin "P$1") (pinfunction "1_P$1") (pintype "passive"))
      (node (ref "IC6") (pin "1") (pinfunction "P$1_1") (pintype "bidirectional"))
      (node (ref "ICSP") (pin "1") (pinfunction "1_1") (pintype "passive"))
      (node (ref "R32") (pin "P$1") (pinfunction "1_P$1") (pintype "passive"))
    )
  )
)
